# dirver2.net
KiCad netlist of a schematic drawn in Altium Designer
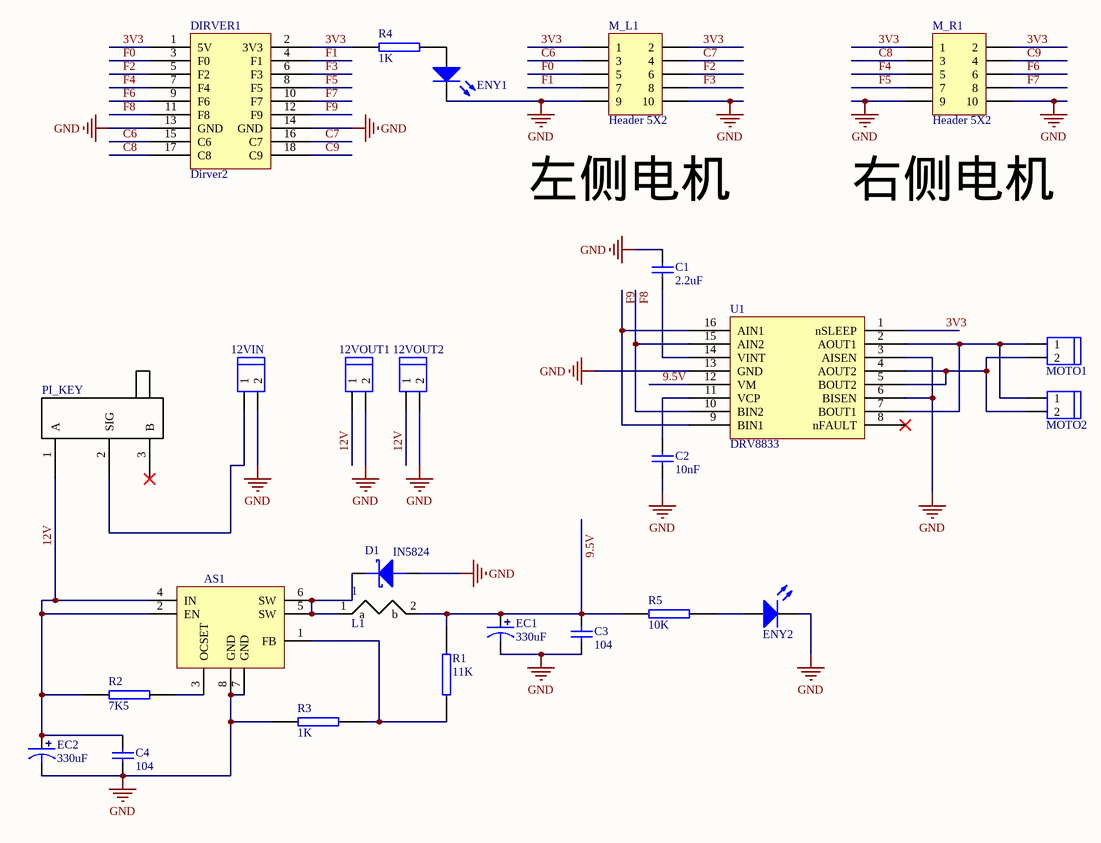
[diagram p0: dirver2.SchDoc]

(export (version "E")
  (design (tool "Eeschema 10.0.6"))
  (components
    (comp (ref "1") (value "L1") (footprint "INDUCTOR") (libsource (lib "robot2") (part "INDUCTOR")))
    (comp (ref "12VIN") (value "HEAD2") (footprint "HEAD2L-0.8") (libsource (lib "robot2") (part "HEAD2")))
    (comp (ref "12VOUT1") (value "HEAD2") (footprint "HEAD2L-0.8") (libsource (lib "robot2") (part "HEAD2")))
    (comp (ref "12VOUT2") (value "HEAD2") (footprint "HEAD2L-0.8") (libsource (lib "robot2") (part "HEAD2")))
    (comp (ref "AS1") (value "U1") (footprint "AS1015") (libsource (lib "输出电压可变直流稳压电源") (part "LED2")))
    (comp (ref "C1")
      (value "Cap")
      (footprint "CAP[0805]")
      (fields (field (name "ALTIUM_UNNAMED_1") "2.2uF"))
      (libsource (lib "Robot") (part "Cap"))
    )
    (comp (ref "C2")
      (value "Cap")
      (footprint "CAP[0805]")
      (fields (field (name "ALTIUM_UNNAMED_1") "10nF"))
      (libsource (lib "Robot") (part "Cap"))
    )
    (comp (ref "C3")
      (value "Cap")
      (footprint "CAP[0805]")
      (fields (field (name "ALTIUM_UNNAMED_1") "104"))
      (libsource (lib "bob") (part "Cap"))
    )
    (comp (ref "C4")
      (value "Cap")
      (footprint "CAP[0805]")
      (fields (field (name "ALTIUM_UNNAMED_1") "104"))
      (libsource (lib "bob") (part "Cap"))
    )
    (comp (ref "D1")
      (value "IN5824")
      (footprint "SMA/DO-214AC")
      (description "肖特基二极管")
      (libsource (lib "bob") (part "DIODE SCHOTTKY"))
    )
    (comp (ref "DIRVER1") (value "Dirver2") (footprint "DIRVER2") (libsource (lib "robot2") (part "Dirver2")))
    (comp (ref "EC1")
      (value "330uF")
      (footprint "DIP-EC5.0X10X12.5")
      (description "直插电解电容")
      (libsource (lib "bob") (part "DIP_ECAP"))
    )
    (comp (ref "EC2")
      (value "330uF")
      (footprint "DIP-EC5.0X10X12.5")
      (description "直插电解电容")
      (libsource (lib "bob") (part "DIP_ECAP"))
    )
    (comp (ref "ENY1") (value "LED0") (footprint "LED[0805]") (libsource (lib "robot2") (part "LED0")))
    (comp (ref "ENY2") (value "LED0") (footprint "LED[0805]") (libsource (lib "robot2") (part "LED0")))
    (comp (ref "MOTO1") (value "HEAD2") (footprint "HEAD2L-0.8") (libsource (lib "Robot") (part "HEAD2")))
    (comp (ref "MOTO2") (value "HEAD2") (footprint "HEAD2L-0.8") (libsource (lib "Robot") (part "HEAD2")))
    (comp (ref "M_L1")
      (value "Header 5X2")
      (footprint "HDR2X5")
      (description "Header, 5-Pin, Dual row")
      (fields (field (name "PUBLISHER") "Altium Limited"))
      (libsource (lib "Miscellaneous Connectors") (part "Header 5X2"))
    )
    (comp (ref "M_R1")
      (value "Header 5X2")
      (footprint "HDR2X5")
      (description "Header, 5-Pin, Dual row")
      (fields (field (name "PUBLISHER") "Altium Limited"))
      (libsource (lib "Miscellaneous Connectors") (part "Header 5X2"))
    )
    (comp (ref "PI_KEY1") (value "PI_KEY") (footprint "KEY") (libsource (lib "robot2") (part "key")))
    (comp (ref "R1") (value "11K") (footprint "R0805") (libsource (lib "bob") (part "RES")))
    (comp (ref "R2") (value "7K5") (footprint "R0805") (libsource (lib "bob") (part "RES")))
    (comp (ref "R3") (value "1K") (footprint "R0805") (libsource (lib "bob") (part "RES")))
    (comp (ref "R4") (value "1K") (footprint "R0805") (libsource (lib "bob") (part "RES")))
    (comp (ref "R5") (value "10K") (footprint "R0805") (libsource (lib "bob") (part "RES")))
    (comp (ref "U1") (value "DRV8833") (footprint "DRV8833") (libsource (lib "dirver2") (part "DRV8833")))
  )
  (nets
    (net (code "1") (name "/3V3") (class "Default")
      (node (ref "DIRVER1") (pin "1") (pinfunction "5V_1") (pintype "passive"))
      (node (ref "DIRVER1") (pin "2") (pinfunction "3V3_2") (pintype "passive"))
      (node (ref "M_L1") (pin "1") (pinfunction "1_1") (pintype "passive"))
      (node (ref "M_L1") (pin "2") (pinfunction "2_2") (pintype "passive"))
      (node (ref "M_R1") (pin "1") (pinfunction "1_1") (pintype "passive"))
      (node (ref "M_R1") (pin "2") (pinfunction "2_2") (pintype "passive"))
      (node (ref "R4") (pin "2") (pinfunction "2_2") (pintype "passive"))
      (node (ref "U1") (pin "1") (pinfunction "nSLEEP_1") (pintype "passive"))
    )
    (net (code "2") (name "/9.5V") (class "Default")
      (node (ref "1") (pin "2") (pinfunction "b_2") (pintype "passive"))
      (node (ref "C3") (pin "2") (pinfunction "2_2") (pintype "passive"))
      (node (ref "EC1") (pin "1") (pinfunction "1_1") (pintype "passive"))
      (node (ref "R1") (pin "2") (pinfunction "2_2") (pintype "passive"))
      (node (ref "R5") (pin "2") (pinfunction "2_2") (pintype "passive"))
      (node (ref "U1") (pin "12") (pinfunction "VM_12") (pintype "passive"))
    )
    (net (code "3") (name "/12V") (class "Default")
      (node (ref "12VOUT1") (pin "1") (pinfunction "1_1") (pintype "passive"))
      (node (ref "12VOUT2") (pin "1") (pinfunction "1_1") (pintype "passive"))
      (node (ref "AS1") (pin "2") (pinfunction "EN_2") (pintype "passive"))
      (node (ref "AS1") (pin "4") (pinfunction "IN_4") (pintype "passive"))
      (node (ref "C4") (pin "2") (pinfunction "2_2") (pintype "passive"))
      (node (ref "EC2") (pin "1") (pinfunction "1_1") (pintype "passive"))
      (node (ref "PI_KEY1") (pin "1") (pinfunction "A_1") (pintype "passive"))
      (node (ref "R2") (pin "1") (pinfunction "1_1") (pintype "passive"))
    )
    (net (code "4") (name "/C6") (class "Default")
      (node (ref "DIRVER1") (pin "15") (pinfunction "C6_15") (pintype "passive"))
      (node (ref "M_L1") (pin "3") (pinfunction "3_3") (pintype "passive"))
    )
    (net (code "5") (name "/C7") (class "Default")
      (node (ref "DIRVER1") (pin "16") (pinfunction "C7_16") (pintype "passive"))
      (node (ref "M_L1") (pin "4") (pinfunction "4_4") (pintype "passive"))
    )
    (net (code "6") (name "/C8") (class "Default")
      (node (ref "DIRVER1") (pin "17") (pinfunction "C8_17") (pintype "passive"))
      (node (ref "M_R1") (pin "3") (pinfunction "3_3") (pintype "passive"))
    )
    (net (code "7") (name "/C9") (class "Default")
      (node (ref "DIRVER1") (pin "18") (pinfunction "C9_18") (pintype "passive"))
      (node (ref "M_R1") (pin "4") (pinfunction "4_4") (pintype "passive"))
    )
    (net (code "8") (name "/F0") (class "Default")
      (node (ref "DIRVER1") (pin "3") (pinfunction "F0_3") (pintype "passive"))
      (node (ref "M_L1") (pin "5") (pinfunction "5_5") (pintype "passive"))
    )
    (net (code "9") (name "/F1") (class "Default")
      (node (ref "DIRVER1") (pin "4") (pinfunction "F1_4") (pintype "passive"))
      (node (ref "M_L1") (pin "7") (pinfunction "7_7") (pintype "passive"))
    )
    (net (code "10") (name "/F2") (class "Default")
      (node (ref "DIRVER1") (pin "5") (pinfunction "F2_5") (pintype "passive"))
      (node (ref "M_L1") (pin "6") (pinfunction "6_6") (pintype "passive"))
    )
    (net (code "11") (name "/F3") (class "Default")
      (node (ref "DIRVER1") (pin "6") (pinfunction "F3_6") (pintype "passive"))
      (node (ref "M_L1") (pin "8") (pinfunction "8_8") (pintype "passive"))
    )
    (net (code "12") (name "/F4") (class "Default")
      (node (ref "DIRVER1") (pin "7") (pinfunction "F4_7") (pintype "passive"))
      (node (ref "M_R1") (pin "5") (pinfunction "5_5") (pintype "passive"))
    )
    (net (code "13") (name "/F5") (class "Default")
      (node (ref "DIRVER1") (pin "8") (pinfunction "F5_8") (pintype "passive"))
      (node (ref "M_R1") (pin "7") (pinfunction "7_7") (pintype "passive"))
    )
    (net (code "14") (name "/F6") (class "Default")
      (node (ref "DIRVER1") (pin "9") (pinfunction "F6_9") (pintype "passive"))
      (node (ref "M_R1") (pin "6") (pinfunction "6_6") (pintype "passive"))
    )
    (net (code "15") (name "/F7") (class "Default")
      (node (ref "DIRVER1") (pin "10") (pinfunction "F7_10") (pintype "passive"))
      (node (ref "M_R1") (pin "8") (pinfunction "8_8") (pintype "passive"))
    )
    (net (code "16") (name "/F8") (class "Default")
      (node (ref "DIRVER1") (pin "11") (pinfunction "F8_11") (pintype "passive"))
      (node (ref "U1") (pin "10") (pinfunction "BIN2_10") (pintype "passive"))
      (node (ref "U1") (pin "15") (pinfunction "AIN2_15") (pintype "passive"))
    )
    (net (code "17") (name "/F9") (class "Default")
      (node (ref "DIRVER1") (pin "12") (pinfunction "F9_12") (pintype "passive"))
      (node (ref "U1") (pin "16") (pinfunction "AIN1_16") (pintype "passive"))
      (node (ref "U1") (pin "9") (pinfunction "BIN1_9") (pintype "passive"))
    )
    (net (code "18") (name "GND") (class "Default")
      (node (ref "12VIN") (pin "2") (pinfunction "2_2") (pintype "passive"))
      (node (ref "12VOUT1") (pin "2") (pinfunction "2_2") (pintype "passive"))
      (node (ref "12VOUT2") (pin "2") (pinfunction "2_2") (pintype "passive"))
      (node (ref "AS1") (pin "7") (pinfunction "GND_7") (pintype "passive"))
      (node (ref "AS1") (pin "8") (pinfunction "GND_8") (pintype "passive"))
      (node (ref "C1") (pin "2") (pinfunction "2_2") (pintype "passive"))
      (node (ref "C2") (pin "1") (pinfunction "1_1") (pintype "passive"))
      (node (ref "C3") (pin "1") (pinfunction "1_1") (pintype "passive"))
      (node (ref "C4") (pin "1") (pinfunction "1_1") (pintype "passive"))
      (node (ref "D1") (pin "A") (pinfunction "A_A") (pintype "passive"))
      (node (ref "DIRVER1") (pin "13") (pinfunction "GND_13") (pintype "passive"))
      (node (ref "DIRVER1") (pin "14") (pinfunction "GND_14") (pintype "passive"))
      (node (ref "EC1") (pin "2") (pinfunction "2_2") (pintype "passive"))
      (node (ref "EC2") (pin "2") (pinfunction "2_2") (pintype "passive"))
      (node (ref "ENY1") (pin "2") (pinfunction "K_2") (pintype "passive"))
      (node (ref "ENY2") (pin "2") (pinfunction "K_2") (pintype "passive"))
      (node (ref "M_L1") (pin "10") (pinfunction "10_10") (pintype "passive"))
      (node (ref "M_L1") (pin "9") (pinfunction "9_9") (pintype "passive"))
      (node (ref "M_R1") (pin "10") (pinfunction "10_10") (pintype "passive"))
      (node (ref "M_R1") (pin "9") (pinfunction "9_9") (pintype "passive"))
      (node (ref "R3") (pin "2") (pinfunction "2_2") (pintype "passive"))
      (node (ref "U1") (pin "13") (pinfunction "GND_13") (pintype "passive"))
      (node (ref "U1") (pin "3") (pinfunction "AISEN_3") (pintype "passive"))
      (node (ref "U1") (pin "6") (pinfunction "BISEN_6") (pintype "passive"))
    )
    (net (code "19") (name "Net-(1-a)") (class "Default")
      (node (ref "1") (pin "1") (pinfunction "a_1") (pintype "passive"))
      (node (ref "AS1") (pin "5") (pinfunction "SW_5") (pintype "passive"))
      (node (ref "AS1") (pin "6") (pinfunction "SW_6") (pintype "passive"))
      (node (ref "D1") (pin "K") (pinfunction "K_K") (pintype "passive"))
    )
    (net (code "20") (name "Net-(AS1-FB)") (class "Default")
      (node (ref "AS1") (pin "1") (pinfunction "FB_1") (pintype "passive"))
      (node (ref "R1") (pin "1") (pinfunction "1_1") (pintype "passive"))
      (node (ref "R3") (pin "1") (pinfunction "1_1") (pintype "passive"))
    )
    (net (code "21") (name "Net-(AS1-OCSET)") (class "Default")
      (node (ref "AS1") (pin "3") (pinfunction "OCSET_3") (pintype "passive"))
      (node (ref "R2") (pin "2") (pinfunction "2_2") (pintype "passive"))
    )
    (net (code "22") (name "Net-(ENY1-A)") (class "Default")
      (node (ref "ENY1") (pin "1") (pinfunction "A_1") (pintype "passive"))
      (node (ref "R4") (pin "1") (pinfunction "1_1") (pintype "passive"))
    )
    (net (code "23") (name "Net-(ENY2-A)") (class "Default")
      (node (ref "ENY2") (pin "1") (pinfunction "A_1") (pintype "passive"))
      (node (ref "R5") (pin "1") (pinfunction "1_1") (pintype "passive"))
    )
    (net (code "24") (name "Net-(PI_KEY1-SIG)") (class "Default")
      (node (ref "12VIN") (pin "1") (pinfunction "1_1") (pintype "passive"))
      (node (ref "PI_KEY1") (pin "2") (pinfunction "SIG_2") (pintype "passive"))
    )
    (net (code "25") (name "Net-(U1-AOUT1)") (class "Default")
      (node (ref "MOTO1") (pin "1") (pinfunction "1_1") (pintype "passive"))
      (node (ref "MOTO2") (pin "1") (pinfunction "1_1") (pintype "passive"))
      (node (ref "U1") (pin "2") (pinfunction "AOUT1_2") (pintype "passive"))
      (node (ref "U1") (pin "7") (pinfunction "BOUT1_7") (pintype "passive"))
    )
    (net (code "26") (name "Net-(U1-AOUT2)") (class "Default")
      (node (ref "MOTO1") (pin "2") (pinfunction "2_2") (pintype "passive"))
      (node (ref "MOTO2") (pin "2") (pinfunction "2_2") (pintype "passive"))
      (node (ref "U1") (pin "4") (pinfunction "AOUT2_4") (pintype "passive"))
      (node (ref "U1") (pin "5") (pinfunction "BOUT2_5") (pintype "passive"))
    )
    (net (code "27") (name "Net-(U1-VCP)") (class "Default")
      (node (ref "C2") (pin "2") (pinfunction "2_2") (pintype "passive"))
      (node (ref "U1") (pin "11") (pinfunction "VCP_11") (pintype "passive"))
    )
    (net (code "28") (name "Net-(U1-VINT)") (class "Default")
      (node (ref "C1") (pin "1") (pinfunction "1_1") (pintype "passive"))
      (node (ref "U1") (pin "14") (pinfunction "VINT_14") (pintype "passive"))
    )
    (net (code "29") (name "unconnected-(PI_KEY1-B-Pad3)") (class "Default")
      (node (ref "PI_KEY1") (pin "3") (pinfunction "B_3") (pintype "passive+no_connect"))
    )
    (net (code "30") (name "unconnected-(U1-nFAULT-Pad8)") (class "Default")
      (node (ref "U1") (pin "8") (pinfunction "nFAULT_8") (pintype "passive+no_connect"))
    )
  )
)
